# HS1-HS2_audio.net
KiCad netlist of a schematic drawn in Altium Designer
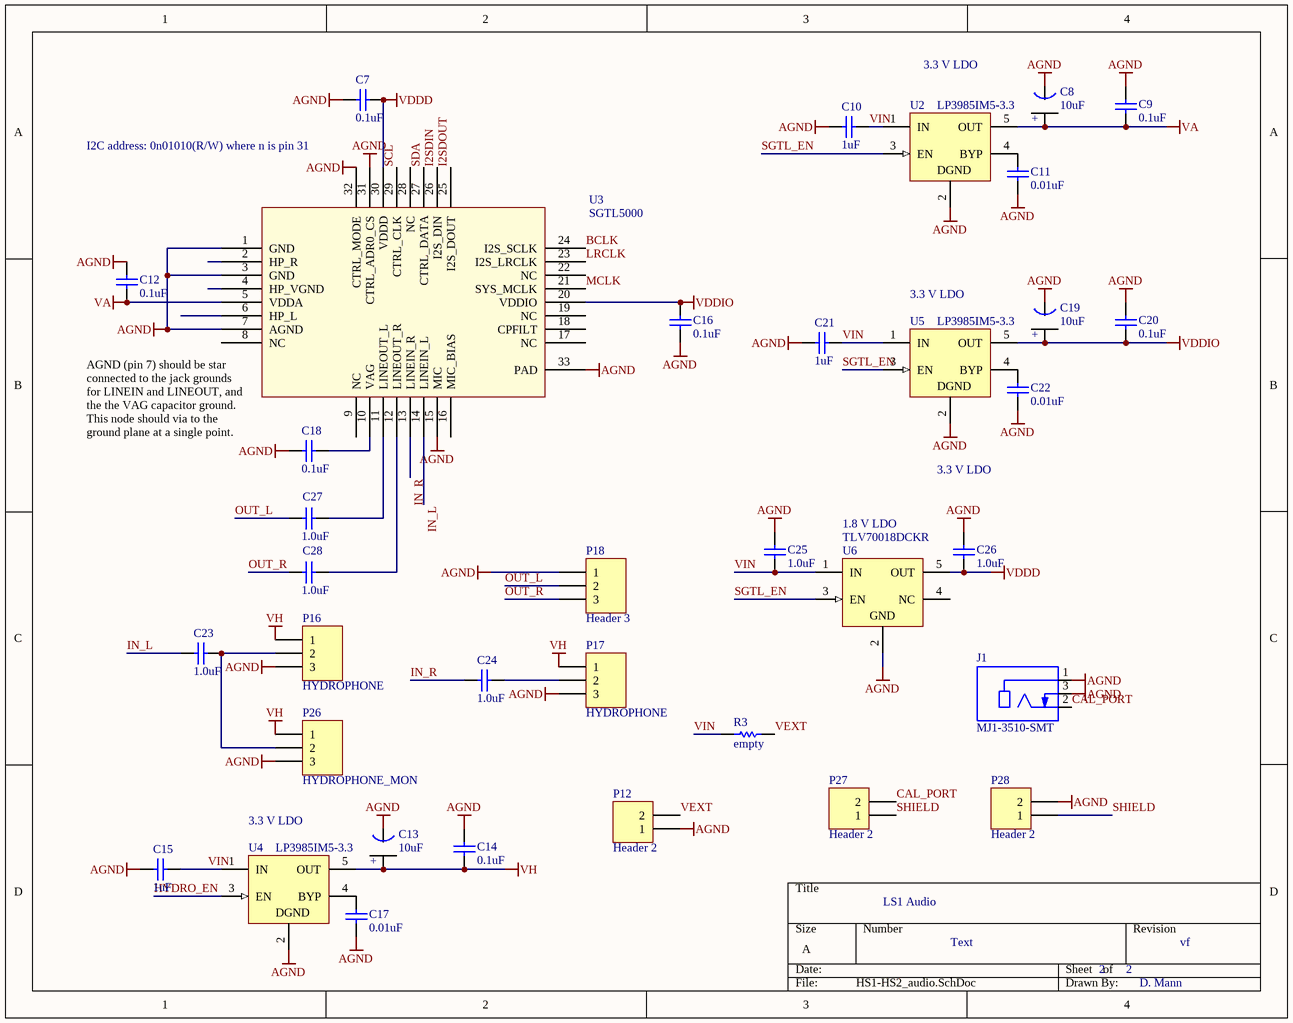
[diagram p0: HS1-HS2_audio.SchDoc]

(export (version "E")
  (design (tool "Eeschema 10.0.6"))
  (components
    (comp (ref "C7")
      (value "0.1uF")
      (footprint "0402")
      (description "Ceramic Chip Capacitor - Standard")
      (fields (field (name "PUBLISHER") "Altium Limited"))
      (libsource (lib "KEMET Chip Capacitor") (part "C0402"))
    )
    (comp (ref "C8") (value "10uF") (footprint "Tant0805") (libsource (lib "Loggerhead") (part "Tant0805")))
    (comp (ref "C9")
      (value "0.1uF")
      (footprint "0402")
      (description "Ceramic Chip Capacitor - Standard")
      (fields (field (name "PUBLISHER") "Altium Limited"))
      (libsource (lib "KEMET Chip Capacitor") (part "C0402"))
    )
    (comp (ref "C10")
      (value "1uF")
      (footprint "0402")
      (description "Ceramic Chip Capacitor - Standard")
      (fields (field (name "PUBLISHER") "Altium Limited"))
      (libsource (lib "KEMET Chip Capacitor") (part "C0402"))
    )
    (comp (ref "C11")
      (value "0.01uF")
      (footprint "0402")
      (description "Ceramic Chip Capacitor - Standard")
      (fields (field (name "PUBLISHER") "Altium Limited"))
      (libsource (lib "KEMET Chip Capacitor") (part "C0402"))
    )
    (comp (ref "C12")
      (value "0.1uF")
      (footprint "0402")
      (description "Ceramic Chip Capacitor - Standard")
      (fields (field (name "PUBLISHER") "Altium Limited"))
      (libsource (lib "KEMET Chip Capacitor") (part "C0402"))
    )
    (comp (ref "C13") (value "10uF") (footprint "Tant0805") (libsource (lib "Loggerhead") (part "Tant0805")))
    (comp (ref "C14")
      (value "0.1uF")
      (footprint "0402")
      (description "Ceramic Chip Capacitor - Standard")
      (fields (field (name "PUBLISHER") "Altium Limited"))
      (libsource (lib "KEMET Chip Capacitor") (part "C0402"))
    )
    (comp (ref "C15")
      (value "1uF")
      (footprint "0402")
      (description "Ceramic Chip Capacitor - Standard")
      (fields (field (name "PUBLISHER") "Altium Limited"))
      (libsource (lib "KEMET Chip Capacitor") (part "C0402"))
    )
    (comp (ref "C16")
      (value "0.1uF")
      (footprint "0402")
      (description "Ceramic Chip Capacitor - Standard")
      (fields (field (name "PUBLISHER") "Altium Limited"))
      (libsource (lib "KEMET Chip Capacitor") (part "C0402"))
    )
    (comp (ref "C17")
      (value "0.01uF")
      (footprint "0402")
      (description "Ceramic Chip Capacitor - Standard")
      (fields (field (name "PUBLISHER") "Altium Limited"))
      (libsource (lib "KEMET Chip Capacitor") (part "C0402"))
    )
    (comp (ref "C18")
      (value "0.1uF")
      (footprint "0402")
      (description "Ceramic Chip Capacitor - Standard")
      (fields (field (name "PUBLISHER") "Altium Limited"))
      (libsource (lib "KEMET Chip Capacitor") (part "C0402"))
    )
    (comp (ref "C19") (value "10uF") (footprint "Tant0805") (libsource (lib "Loggerhead") (part "Tant0805")))
    (comp (ref "C20")
      (value "0.1uF")
      (footprint "0402")
      (description "Ceramic Chip Capacitor - Standard")
      (fields (field (name "PUBLISHER") "Altium Limited"))
      (libsource (lib "KEMET Chip Capacitor") (part "C0402"))
    )
    (comp (ref "C21")
      (value "1uF")
      (footprint "0402")
      (description "Ceramic Chip Capacitor - Standard")
      (fields (field (name "PUBLISHER") "Altium Limited"))
      (libsource (lib "KEMET Chip Capacitor") (part "C0402"))
    )
    (comp (ref "C22")
      (value "0.01uF")
      (footprint "0402")
      (description "Ceramic Chip Capacitor - Standard")
      (fields (field (name "PUBLISHER") "Altium Limited"))
      (libsource (lib "KEMET Chip Capacitor") (part "C0402"))
    )
    (comp (ref "C23")
      (value "1.0uF")
      (footprint "0402")
      (description "Ceramic Chip Capacitor - Standard")
      (fields (field (name "PUBLISHER") "Altium Limited"))
      (libsource (lib "KEMET Chip Capacitor") (part "C0402"))
    )
    (comp (ref "C24")
      (value "1.0uF")
      (footprint "0402")
      (description "Ceramic Chip Capacitor - Standard")
      (fields (field (name "PUBLISHER") "Altium Limited"))
      (libsource (lib "KEMET Chip Capacitor") (part "C0402"))
    )
    (comp (ref "C25")
      (value "1.0uF")
      (footprint "0402")
      (description "Ceramic Chip Capacitor - Standard")
      (fields (field (name "PUBLISHER") "Altium Limited"))
      (libsource (lib "KEMET Chip Capacitor") (part "C0402"))
    )
    (comp (ref "C26")
      (value "1.0uF")
      (footprint "0402")
      (description "Ceramic Chip Capacitor - Standard")
      (fields (field (name "PUBLISHER") "Altium Limited"))
      (libsource (lib "KEMET Chip Capacitor") (part "C0402"))
    )
    (comp (ref "C27")
      (value "1.0uF")
      (footprint "0402")
      (description "Ceramic Chip Capacitor - Standard")
      (fields (field (name "PUBLISHER") "Altium Limited"))
      (libsource (lib "KEMET Chip Capacitor") (part "C0402"))
    )
    (comp (ref "C28")
      (value "1.0uF")
      (footprint "0402")
      (description "Ceramic Chip Capacitor - Standard")
      (fields (field (name "PUBLISHER") "Altium Limited"))
      (libsource (lib "KEMET Chip Capacitor") (part "C0402"))
    )
    (comp (ref "J1")
      (value "MJ1-3510-SMT")
      (footprint "CUI_MJ1-3510-SMT")
      (description "3.5 mm, Mono, Right Angle, Surface Mount (SMT), Audio Jack Connector")
      (fields (field (name "MF") "{'manufacturer': u'CUI'}"))
      (libsource (lib "MJ1-3510-SMT") (part "MJ1-3510-SMT"))
    )
    (comp (ref "P12")
      (value "Header 2")
      (footprint "HDR1X2")
      (description "Header, 2-Pin")
      (fields (field (name "PUBLISHER") "Altium Limited"))
      (libsource (lib "Miscellaneous Connectors") (part "Header 2"))
    )
    (comp (ref "P16")
      (value "HYDROPHONE")
      (footprint "HDR1X3")
      (description "Header, 3-Pin")
      (fields (field (name "PUBLISHER") "Altium Limited"))
      (libsource (lib "Miscellaneous Connectors") (part "Header 3"))
    )
    (comp (ref "P17")
      (value "HYDROPHONE")
      (footprint "HDR1X3")
      (description "Header, 3-Pin")
      (fields (field (name "PUBLISHER") "Altium Limited"))
      (libsource (lib "Miscellaneous Connectors") (part "Header 3"))
    )
    (comp (ref "P18")
      (value "Header 3")
      (footprint "HDR1X3")
      (description "Header, 3-Pin")
      (fields (field (name "PUBLISHER") "Altium Limited"))
      (libsource (lib "Miscellaneous Connectors") (part "Header 3"))
    )
    (comp (ref "P26")
      (value "HYDROPHONE_MON")
      (footprint "HDR1X3")
      (description "Header, 3-Pin")
      (fields (field (name "PUBLISHER") "Altium Limited"))
      (libsource (lib "Miscellaneous Connectors") (part "Header 3"))
    )
    (comp (ref "P27")
      (value "Header 2")
      (footprint "HDR1X2")
      (description "Header, 2-Pin")
      (fields (field (name "PUBLISHER") "Altium Limited"))
      (libsource (lib "Miscellaneous Connectors") (part "Header 2"))
    )
    (comp (ref "P28")
      (value "Header 2")
      (footprint "HDR1X2")
      (description "Header, 2-Pin")
      (fields (field (name "PUBLISHER") "Altium Limited"))
      (libsource (lib "Miscellaneous Connectors") (part "Header 2"))
    )
    (comp (ref "R3")
      (value "empty")
      (footprint "3-0603")
      (fields (field (name "PUBLISHER") "Altium Limited"))
      (libsource (lib "Panasonic Resistor") (part "ERJ3RK"))
    )
    (comp (ref "U2")
      (value "LP3985IM5-3.3")
      (footprint "MF05A_N")
      (description "Micropower, 150mA Low-Noise Ultra Low-Dropout CMOS Voltage Regulator")
      (fields
        (field (name "MANUFACTURER") "National Semiconductor")
        (field (name "DIGIKEYPARTNUMBER") "LP3985IM5-3.3CT-ND")
        (field (name "PUBLISHER") "Altium Limited")
      )
      (libsource (lib "NSC LDO") (part "LP3985IM5-3.3"))
    )
    (comp (ref "U3") (value "SGTL5000") (footprint "QFN32") (libsource (lib "Loggerhead") (part "SGTL5000")))
    (comp (ref "U4")
      (value "LP3985IM5-3.3")
      (footprint "MF05A_N")
      (description "Micropower, 150mA Low-Noise Ultra Low-Dropout CMOS Voltage Regulator")
      (fields
        (field (name "MANUFACTURER") "National Semiconductor")
        (field (name "DIGIKEYPARTNUMBER") "LP3985IM5-3.3CT-ND")
        (field (name "PUBLISHER") "Altium Limited")
      )
      (libsource (lib "NSC LDO") (part "LP3985IM5-3.3"))
    )
    (comp (ref "U5")
      (value "LP3985IM5-3.3")
      (footprint "MF05A_N")
      (description "Micropower, 150mA Low-Noise Ultra Low-Dropout CMOS Voltage Regulator")
      (fields
        (field (name "MANUFACTURER") "National Semiconductor")
        (field (name "DIGIKEYPARTNUMBER") "LP3985IM5-3.3CT-ND")
        (field (name "PUBLISHER") "Altium Limited")
      )
      (libsource (lib "NSC LDO") (part "LP3985IM5-3.3"))
    )
    (comp (ref "U6")
      (value "TLV70018DCKR")
      (footprint "TI-DCK5_V")
      (fields (field (name "MANUFACTURER") "Texas Instruments"))
      (libsource (lib "TI Power Management Linear Regulator Single Channel LDO (0-350mA)") (part "TLV70018DCKR"))
    )
  )
  (nets
    (net (code "1") (name "/BCLK") (class "Default")
      (node (ref "U3") (pin "24") (pinfunction "I2S_SCLK_24") (pintype "passive"))
    )
    (net (code "2") (name "/CAL_PORT") (class "Default")
      (node (ref "J1") (pin "2") (pinfunction "2_2") (pintype "passive"))
      (node (ref "P27") (pin "2") (pinfunction "2_2") (pintype "passive"))
    )
    (net (code "3") (name "/HYDRO_EN") (class "Default")
      (node (ref "U4") (pin "3") (pinfunction "EN_3") (pintype "input"))
    )
    (net (code "4") (name "/I2SDIN") (class "Default")
      (node (ref "U3") (pin "26") (pinfunction "I2S_DIN_26") (pintype "passive"))
    )
    (net (code "5") (name "/I2SDOUT") (class "Default")
      (node (ref "U3") (pin "25") (pinfunction "I2S_DOUT_25") (pintype "passive"))
    )
    (net (code "6") (name "/IN_L") (class "Default")
      (node (ref "C23") (pin "2") (pinfunction "2_2") (pintype "passive"))
      (node (ref "U3") (pin "14") (pinfunction "LINEIN_L_14") (pintype "passive"))
    )
    (net (code "7") (name "/IN_R") (class "Default")
      (node (ref "C24") (pin "2") (pinfunction "2_2") (pintype "passive"))
      (node (ref "U3") (pin "13") (pinfunction "LINEIN_R_13") (pintype "passive"))
    )
    (net (code "8") (name "/LRCLK") (class "Default")
      (node (ref "U3") (pin "23") (pinfunction "I2S_LRCLK_23") (pintype "passive"))
    )
    (net (code "9") (name "/MCLK") (class "Default")
      (node (ref "U3") (pin "21") (pinfunction "SYS_MCLK_21") (pintype "passive"))
    )
    (net (code "10") (name "/OUT_L") (class "Default")
      (node (ref "C27") (pin "1") (pinfunction "1_1") (pintype "passive"))
      (node (ref "P18") (pin "2") (pinfunction "2_2") (pintype "passive"))
    )
    (net (code "11") (name "/OUT_R") (class "Default")
      (node (ref "C28") (pin "1") (pinfunction "1_1") (pintype "passive"))
      (node (ref "P18") (pin "3") (pinfunction "3_3") (pintype "passive"))
    )
    (net (code "12") (name "/SCL") (class "Default")
      (node (ref "U3") (pin "29") (pinfunction "CTRL_CLK_29") (pintype "passive"))
    )
    (net (code "13") (name "/SDA") (class "Default")
      (node (ref "U3") (pin "27") (pinfunction "CTRL_DATA_27") (pintype "passive"))
    )
    (net (code "14") (name "/SGTL_EN") (class "Default")
      (node (ref "U2") (pin "3") (pinfunction "EN_3") (pintype "input"))
      (node (ref "U5") (pin "3") (pinfunction "EN_3") (pintype "input"))
      (node (ref "U6") (pin "3") (pinfunction "EN_3") (pintype "input"))
    )
    (net (code "15") (name "/SHIELD") (class "Default")
      (node (ref "P27") (pin "1") (pinfunction "1_1") (pintype "passive"))
      (node (ref "P28") (pin "1") (pinfunction "1_1") (pintype "passive"))
    )
    (net (code "16") (name "/VEXT") (class "Default")
      (node (ref "P12") (pin "2") (pinfunction "2_2") (pintype "passive"))
      (node (ref "R3") (pin "1") (pinfunction "1_1") (pintype "passive"))
    )
    (net (code "17") (name "/VIN") (class "Default")
      (node (ref "C10") (pin "1") (pinfunction "1_1") (pintype "passive"))
      (node (ref "C15") (pin "1") (pinfunction "1_1") (pintype "passive"))
      (node (ref "C21") (pin "1") (pinfunction "1_1") (pintype "passive"))
      (node (ref "C25") (pin "1") (pinfunction "1_1") (pintype "passive"))
      (node (ref "R3") (pin "2") (pinfunction "2_2") (pintype "passive"))
      (node (ref "U2") (pin "1") (pinfunction "IN_1") (pintype "power_in"))
      (node (ref "U4") (pin "1") (pinfunction "IN_1") (pintype "power_in"))
      (node (ref "U5") (pin "1") (pinfunction "IN_1") (pintype "power_in"))
      (node (ref "U6") (pin "1") (pinfunction "IN_1") (pintype "power_in"))
    )
    (net (code "18") (name "AGND") (class "Default")
      (node (ref "C10") (pin "2") (pinfunction "2_2") (pintype "passive"))
      (node (ref "C11") (pin "2") (pinfunction "2_2") (pintype "passive"))
      (node (ref "C12") (pin "2") (pinfunction "2_2") (pintype "passive"))
      (node (ref "C13") (pin "1") (pinfunction "GND_1") (pintype "passive"))
      (node (ref "C14") (pin "2") (pinfunction "2_2") (pintype "passive"))
      (node (ref "C15") (pin "2") (pinfunction "2_2") (pintype "passive"))
      (node (ref "C16") (pin "2") (pinfunction "2_2") (pintype "passive"))
      (node (ref "C17") (pin "2") (pinfunction "2_2") (pintype "passive"))
      (node (ref "C18") (pin "2") (pinfunction "2_2") (pintype "passive"))
      (node (ref "C19") (pin "1") (pinfunction "GND_1") (pintype "passive"))
      (node (ref "C20") (pin "2") (pinfunction "2_2") (pintype "passive"))
      (node (ref "C21") (pin "2") (pinfunction "2_2") (pintype "passive"))
      (node (ref "C22") (pin "2") (pinfunction "2_2") (pintype "passive"))
      (node (ref "C25") (pin "2") (pinfunction "2_2") (pintype "passive"))
      (node (ref "C26") (pin "2") (pinfunction "2_2") (pintype "passive"))
      (node (ref "C7") (pin "2") (pinfunction "2_2") (pintype "passive"))
      (node (ref "C8") (pin "1") (pinfunction "GND_1") (pintype "passive"))
      (node (ref "C9") (pin "2") (pinfunction "2_2") (pintype "passive"))
      (node (ref "J1") (pin "1") (pinfunction "1_1") (pintype "passive"))
      (node (ref "J1") (pin "3") (pinfunction "3_3") (pintype "passive"))
      (node (ref "P12") (pin "1") (pinfunction "1_1") (pintype "passive"))
      (node (ref "P16") (pin "3") (pinfunction "3_3") (pintype "passive"))
      (node (ref "P17") (pin "3") (pinfunction "3_3") (pintype "passive"))
      (node (ref "P18") (pin "1") (pinfunction "1_1") (pintype "passive"))
      (node (ref "P26") (pin "3") (pinfunction "3_3") (pintype "passive"))
      (node (ref "P28") (pin "2") (pinfunction "2_2") (pintype "passive"))
      (node (ref "U2") (pin "2") (pinfunction "GND_2") (pintype "power_in"))
      (node (ref "U3") (pin "1") (pinfunction "GND_1") (pintype "passive"))
      (node (ref "U3") (pin "15") (pinfunction "MIC_15") (pintype "passive"))
      (node (ref "U3") (pin "3") (pinfunction "GND_3") (pintype "passive"))
      (node (ref "U3") (pin "31") (pinfunction "CTRL_ADR0_CS_31") (pintype "passive"))
      (node (ref "U3") (pin "32") (pinfunction "CTRL_MODE_32") (pintype "passive"))
      (node (ref "U3") (pin "33") (pinfunction "PAD_33") (pintype "passive"))
      (node (ref "U3") (pin "7") (pinfunction "AGND_7") (pintype "passive"))
      (node (ref "U4") (pin "2") (pinfunction "GND_2") (pintype "power_in"))
      (node (ref "U5") (pin "2") (pinfunction "GND_2") (pintype "power_in"))
      (node (ref "U6") (pin "2") (pinfunction "GND_2") (pintype "power_in"))
    )
    (net (code "19") (name "Net-(C23-Pad1)") (class "Default")
      (node (ref "C23") (pin "1") (pinfunction "1_1") (pintype "passive"))
      (node (ref "P16") (pin "2") (pinfunction "2_2") (pintype "passive"))
      (node (ref "P26") (pin "2") (pinfunction "2_2") (pintype "passive"))
    )
    (net (code "20") (name "Net-(C24-Pad1)") (class "Default")
      (node (ref "C24") (pin "1") (pinfunction "1_1") (pintype "passive"))
      (node (ref "P17") (pin "2") (pinfunction "2_2") (pintype "passive"))
    )
    (net (code "21") (name "Net-(U2-BYP)") (class "Default")
      (node (ref "C11") (pin "1") (pinfunction "1_1") (pintype "passive"))
      (node (ref "U2") (pin "4") (pinfunction "BYP_4") (pintype "passive"))
    )
    (net (code "22") (name "Net-(U3-LINEOUT_L)") (class "Default")
      (node (ref "C27") (pin "2") (pinfunction "2_2") (pintype "passive"))
      (node (ref "U3") (pin "11") (pinfunction "LINEOUT_L_11") (pintype "passive"))
    )
    (net (code "23") (name "Net-(U3-LINEOUT_R)") (class "Default")
      (node (ref "C28") (pin "2") (pinfunction "2_2") (pintype "passive"))
      (node (ref "U3") (pin "12") (pinfunction "LINEOUT_R_12") (pintype "passive"))
    )
    (net (code "24") (name "Net-(U3-VAG)") (class "Default")
      (node (ref "C18") (pin "1") (pinfunction "1_1") (pintype "passive"))
      (node (ref "U3") (pin "10") (pinfunction "VAG_10") (pintype "passive"))
    )
    (net (code "25") (name "Net-(U4-BYP)") (class "Default")
      (node (ref "C17") (pin "1") (pinfunction "1_1") (pintype "passive"))
      (node (ref "U4") (pin "4") (pinfunction "BYP_4") (pintype "passive"))
    )
    (net (code "26") (name "Net-(U5-BYP)") (class "Default")
      (node (ref "C22") (pin "1") (pinfunction "1_1") (pintype "passive"))
      (node (ref "U5") (pin "4") (pinfunction "BYP_4") (pintype "passive"))
    )
    (net (code "27") (name "VA") (class "Default")
      (node (ref "C12") (pin "1") (pinfunction "1_1") (pintype "passive"))
      (node (ref "C8") (pin "2") (pinfunction "+_2") (pintype "passive"))
      (node (ref "C9") (pin "1") (pinfunction "1_1") (pintype "passive"))
      (node (ref "U2") (pin "5") (pinfunction "OUT_5") (pintype "power_in"))
      (node (ref "U3") (pin "5") (pinfunction "VDDA_5") (pintype "passive"))
    )
    (net (code "28") (name "VDDD") (class "Default")
      (node (ref "C26") (pin "1") (pinfunction "1_1") (pintype "passive"))
      (node (ref "C7") (pin "1") (pinfunction "1_1") (pintype "passive"))
      (node (ref "U3") (pin "30") (pinfunction "VDDD_30") (pintype "passive"))
      (node (ref "U6") (pin "5") (pinfunction "OUT_5") (pintype "power_in"))
    )
    (net (code "29") (name "VDDIO") (class "Default")
      (node (ref "C16") (pin "1") (pinfunction "1_1") (pintype "passive"))
      (node (ref "C19") (pin "2") (pinfunction "+_2") (pintype "passive"))
      (node (ref "C20") (pin "1") (pinfunction "1_1") (pintype "passive"))
      (node (ref "U3") (pin "20") (pinfunction "VDDIO_20") (pintype "passive"))
      (node (ref "U5") (pin "5") (pinfunction "OUT_5") (pintype "power_in"))
    )
    (net (code "30") (name "VH") (class "Default")
      (node (ref "C13") (pin "2") (pinfunction "+_2") (pintype "passive"))
      (node (ref "C14") (pin "1") (pinfunction "1_1") (pintype "passive"))
      (node (ref "P16") (pin "1") (pinfunction "1_1") (pintype "passive"))
      (node (ref "P17") (pin "1") (pinfunction "1_1") (pintype "passive"))
      (node (ref "P26") (pin "1") (pinfunction "1_1") (pintype "passive"))
      (node (ref "U4") (pin "5") (pinfunction "OUT_5") (pintype "power_in"))
    )
    (net (code "31") (name "unconnected-(U3-CPFILT-Pad18)") (class "Default")
      (node (ref "U3") (pin "18") (pinfunction "CPFILT_18") (pintype "passive"))
    )
    (net (code "32") (name "unconnected-(U3-HP_L-Pad6)") (class "Default")
      (node (ref "U3") (pin "6") (pinfunction "HP_L_6") (pintype "passive"))
    )
    (net (code "33") (name "unconnected-(U3-HP_R-Pad2)") (class "Default")
      (node (ref "U3") (pin "2") (pinfunction "HP_R_2") (pintype "passive"))
    )
    (net (code "34") (name "unconnected-(U3-HP_VGND-Pad4)") (class "Default")
      (node (ref "U3") (pin "4") (pinfunction "HP_VGND_4") (pintype "passive"))
    )
    (net (code "35") (name "unconnected-(U3-MIC_BIAS-Pad16)") (class "Default")
      (node (ref "U3") (pin "16") (pinfunction "MIC_BIAS_16") (pintype "passive"))
    )
    (net (code "36") (name "unconnected-(U3-NC-Pad8)") (class "Default")
      (node (ref "U3") (pin "8") (pinfunction "NC_8") (pintype "passive"))
    )
    (net (code "37") (name "unconnected-(U3-NC-Pad9)") (class "Default")
      (node (ref "U3") (pin "9") (pinfunction "NC_9") (pintype "passive"))
    )
    (net (code "38") (name "unconnected-(U3-NC-Pad17)") (class "Default")
      (node (ref "U3") (pin "17") (pinfunction "NC_17") (pintype "passive"))
    )
    (net (code "39") (name "unconnected-(U3-NC-Pad19)") (class "Default")
      (node (ref "U3") (pin "19") (pinfunction "NC_19") (pintype "passive"))
    )
    (net (code "40") (name "unconnected-(U3-NC-Pad22)") (class "Default")
      (node (ref "U3") (pin "22") (pinfunction "NC_22") (pintype "passive"))
    )
    (net (code "41") (name "unconnected-(U3-NC-Pad28)") (class "Default")
      (node (ref "U3") (pin "28") (pinfunction "NC_28") (pintype "passive"))
    )
    (net (code "42") (name "unconnected-(U6-NC-Pad4)") (class "Default")
      (node (ref "U6") (pin "4") (pinfunction "NC_4") (pintype "passive"))
    )
  )
)
